# USBC_B.net
KiCad netlist of a schematic drawn in Altium Designer
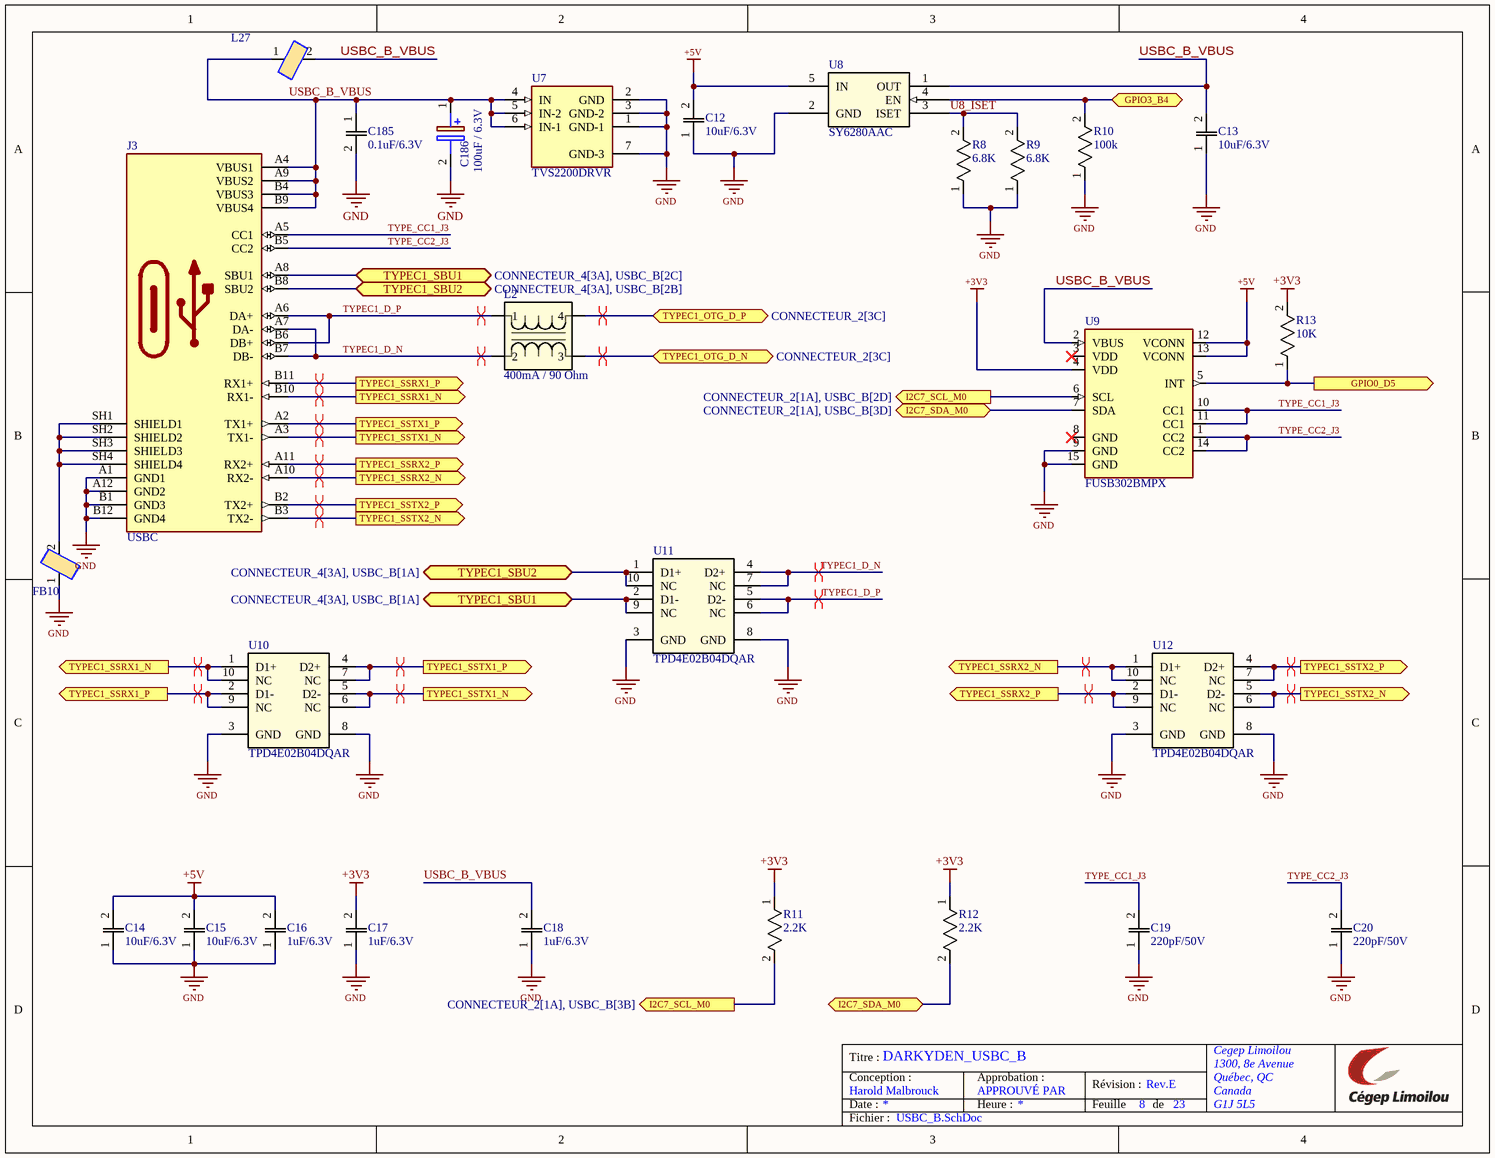
[diagram p0: USBC_B.SchDoc]

(export (version "E")
  (design (tool "Eeschema 10.0.6"))
  (components
    (comp (ref "C12")
      (value "10uF/6.3V")
      (footprint "C0805")
      (fields
        (field (name "MANUFACTURER_PART_NUMBER") "C0805C106K9RACTU")
        (field (name "MOUSER PART NUMBER") "80-C0805C106K9R")
        (field (name "MANUFACTURER") "KEMET")
      )
      (libsource (lib "DARKYDEN") (part "C0805C106K9RACTU"))
    )
    (comp (ref "C13")
      (value "10uF/6.3V")
      (footprint "C0805")
      (fields
        (field (name "MANUFACTURER_PART_NUMBER") "C0805C106K9RACTU")
        (field (name "MOUSER PART NUMBER") "80-C0805C106K9R")
        (field (name "MANUFACTURER") "KEMET")
      )
      (libsource (lib "DARKYDEN") (part "C0805C106K9RACTU"))
    )
    (comp (ref "C14")
      (value "10uF/6.3V")
      (footprint "C0805")
      (fields
        (field (name "MANUFACTURER_PART_NUMBER") "C0805C106K9RACTU")
        (field (name "MOUSER PART NUMBER") "80-C0805C106K9R")
        (field (name "MANUFACTURER") "KEMET")
      )
      (libsource (lib "DARKYDEN") (part "C0805C106K9RACTU"))
    )
    (comp (ref "C15")
      (value "10uF/6.3V")
      (footprint "C0805")
      (fields
        (field (name "MANUFACTURER_PART_NUMBER") "C0805C106K9RACTU")
        (field (name "MOUSER PART NUMBER") "80-C0805C106K9R")
        (field (name "MANUFACTURER") "KEMET")
      )
      (libsource (lib "DARKYDEN") (part "C0805C106K9RACTU"))
    )
    (comp (ref "C16")
      (value "1uF/6.3V")
      (footprint "C0805")
      (description "1 uF, 6.3 V, ± 10%, X7R, 0805 [2012 Metric] Multilayer Ceramic Capacitor,")
      (fields
        (field (name "MANUFACTURER_PART_NUMBER") "C0805C105K9RACTU")
        (field (name "MOUSER PART NUMBER") "80-C0805C105K9R")
      )
      (libsource (lib "DARKYDEN") (part "C0805C105K9RACTU"))
    )
    (comp (ref "C17")
      (value "1uF/6.3V")
      (footprint "C0805")
      (description "1 uF, 6.3 V, ± 10%, X7R, 0805 [2012 Metric] Multilayer Ceramic Capacitor,")
      (fields
        (field (name "MANUFACTURER_PART_NUMBER") "C0805C105K9RACTU")
        (field (name "MOUSER PART NUMBER") "80-C0805C105K9R")
      )
      (libsource (lib "DARKYDEN") (part "C0805C105K9RACTU"))
    )
    (comp (ref "C18")
      (value "1uF/6.3V")
      (footprint "C0805")
      (description "1 uF, 6.3 V, ± 10%, X7R, 0805 [2012 Metric] Multilayer Ceramic Capacitor,")
      (fields
        (field (name "MANUFACTURER_PART_NUMBER") "C0805C105K9RACTU")
        (field (name "MOUSER PART NUMBER") "80-C0805C105K9R")
      )
      (libsource (lib "DARKYDEN") (part "C0805C105K9RACTU"))
    )
    (comp (ref "C19")
      (value "220pF/50V")
      (footprint "C0805")
      (description "Cap Ceramic 220pF 50V X7R 20% Pad SMD 0805 125C T/R")
      (fields
        (field (name "MANUFACTURER") "KEMET")
        (field (name "MANUFACTURER PART NUMBER") "C0805C221M5RACTU")
      )
      (libsource (lib "DARKYDEN") (part "C0805C221M5RACTU"))
    )
    (comp (ref "C20")
      (value "220pF/50V")
      (footprint "C0805")
      (description "Cap Ceramic 220pF 50V X7R 20% Pad SMD 0805 125C T/R")
      (fields
        (field (name "MANUFACTURER") "KEMET")
        (field (name "MANUFACTURER PART NUMBER") "C0805C221M5RACTU")
      )
      (libsource (lib "DARKYDEN") (part "C0805C221M5RACTU"))
    )
    (comp (ref "C185")
      (value "0.1uF/6.3V")
      (footprint "C0805")
      (description "0.1uF 6.3V X7R 10% Pad SMD 0805 125C T/R")
      (fields
        (field (name "MANUFACTURER_PART_NUMBER") "C0805C104K9RACTU")
        (field (name "MOUSER PART NUMBER") "80-C0805C104K9R")
      )
      (libsource (lib "DARKYDEN") (part "C0805C104K9RACTU"))
    )
    (comp (ref "C186")
      (value "100uF / 6.3V")
      (footprint "SamacSys:EEE0GA101SR")
      (description "100uF 6.3V 20% Cap Aluminum Lytic  SMD 0.36 Ohm 240mA 2000h 105C Automotive T/R")
      (fields
        (field (name "MANUFACTURER_PART_NUMBER") "EEE-FPJ101UAR")
        (field (name "MOUSER PART NUMBER") "667-EEE-FPJ101UAR")
      )
      (libsource (lib "SamacSys") (part "EEE-FPJ101UAR"))
    )
    (comp (ref "FB10")
      (value "220R / 100MHz")
      (footprint "SamacSys:BLM18SP221SN1B")
      (description "Ferrite Beads Multi-Layer 220Ohm 25% 100MHz 2A 50mOhm DCR 0603 Paper T/R")
      (fields
        (field (name "MANUFACTURER_PART_NUMBER") "BLM18EG221SN1D")
        (field (name "MOUSER PART NUMBER") "81-BLM18EG221SN1D")
      )
      (libsource (lib "SamacSys") (part "BLM18EG221SN1D"))
    )
    (comp (ref "J3")
      (value "USBC")
      (footprint "USB_C")
      (fields (field (name "MF") "Molex") (field (name "MP") "2012670005"))
      (libsource (lib "DARKYDEN") (part "USBC"))
    )
    (comp (ref "L2")
      (value "400mA / 90 Ohm")
      (footprint "SamacSys:ACM20129002PT002")
      (description "Ferrite Beads Wirewound Common Mode Filter 90Ohm 100MHz 400mA 0805 T/R")
      (fields
        (field (name "MANUFACTURER_PART_NUMBER") "ACM2012-900-2P-T002")
        (field (name "MOUSER PART NUMBER") "810-ACM20129002PT002")
      )
      (libsource (lib "SamacSys") (part "ACM2012-900-2P-T002"))
    )
    (comp (ref "L27")
      (value "FBMJ2125HM210NT")
      (footprint "INDC2012X105N")
      (description "Ferrite Beads Power Chip 21Ohm 30% 100MHz 6A 0.004Ohm DCR 0805 Automotive T/R")
      (fields
        (field (name "MANUFACTURER") "Taiyo Yuden")
        (field (name "MOUSER PART NUMBER") "963-FBMJ2125HM210NT")
      )
      (libsource (lib "SamacSys") (part "FBMJ2125HM210NT"))
    )
    (comp (ref "R8")
      (value "6.8K")
      (footprint "SamacSys:RESC1608X55N")
      (description "6.8 kOhm, ± 5%, 100 mW, 0603 [1608 Metric], Thick Film, General Purpose")
      (fields
        (field (name "MANUFACTURER_PART_NUMBER") "ERJ-3GEYJ682V")
        (field (name "MANUFACTURER") "Panasonic")
      )
      (libsource (lib "DARKYDEN") (part "ERJ-3GEYJ682V"))
    )
    (comp (ref "R9")
      (value "6.8K")
      (footprint "SamacSys:RESC1608X55N")
      (description "6.8 kOhm, ± 5%, 100 mW, 0603 [1608 Metric], Thick Film, General Purpose")
      (fields
        (field (name "MANUFACTURER_PART_NUMBER") "ERJ-3GEYJ682V")
        (field (name "MANUFACTURER") "Panasonic")
      )
      (libsource (lib "DARKYDEN") (part "ERJ-3GEYJ682V"))
    )
    (comp (ref "R10")
      (value "100k")
      (footprint "SamacSys:RESC1608X55N")
      (description "100K Ohm 5%  Res Thick Film 0603 1/10W +/-200ppm/ßC Molded SMD Punched Carrier T/R")
      (fields
        (field (name "MANUFACTURER_PART_NUMBER") "ERJ-3GEYJ104V")
        (field (name "MOUSER PART NUMBER") "667-ERJ-3GEYJ104V")
      )
      (libsource (lib "DARKYDEN") (part "ERJ-3GEYJ104V"))
    )
    (comp (ref "R11")
      (value "2.2K")
      (footprint "SamacSys:RESC1608X55N")
      (description "2.2 kOhm, ï¿½ 5%, 100 mW, 0603 [1608 Metric], Thick Film, General Purpose")
      (fields
        (field (name "MANUFACTURER_PART_NUMBER") "ERJ-3GEYJ222V")
        (field (name "MOUSER PART NUMBER") "667-ERJ-3GEYJ222V")
      )
      (libsource (lib "DARKYDEN") (part "ERJ-3GEYJ222V"))
    )
    (comp (ref "R12")
      (value "2.2K")
      (footprint "SamacSys:RESC1608X55N")
      (description "2.2 kOhm, ï¿½ 5%, 100 mW, 0603 [1608 Metric], Thick Film, General Purpose")
      (fields
        (field (name "MANUFACTURER_PART_NUMBER") "ERJ-3GEYJ222V")
        (field (name "MOUSER PART NUMBER") "667-ERJ-3GEYJ222V")
      )
      (libsource (lib "DARKYDEN") (part "ERJ-3GEYJ222V"))
    )
    (comp (ref "R13")
      (value "10K")
      (footprint "SamacSys:RESC1608X55N")
      (description "10K Ohm 5% Res Thick Film 0603  0.1W(1/10W) ±200ppm/C Pad SMD Automotive T/R")
      (fields
        (field (name "MANUFACTURER_PART_NUMBER") "ERJ-3GEYJ103V")
        (field (name "MOUSER PART NUMBER") "667-ERJ-3GEYJ103V")
      )
      (libsource (lib "DARKYDEN") (part "ERJ-3GEYJ103V"))
    )
    (comp (ref "U7")
      (value "TVS2200DRVR")
      (footprint "SON65P200X200X80-7N")
      (description "ESD Suppressors / TVS Diodes 22V flat-clamp surge protection device 6-WSON -40 to 125")
      (fields (field (name "MF") "Texas Instruments"))
      (libsource (lib "TVS2200") (part "TVS2200DRVR"))
    )
    (comp (ref "U8")
      (value "SY6280AAC")
      (footprint "SamacSys:SOT95P285X140-5N")
      (description "2.4V~5.5V 80mΩ Active High 1 High-side switch SOT-23-5 Power Distribution Switches ROHS")
      (libsource (lib "SamacSys") (part "SY6280AAC"))
    )
    (comp (ref "U9")
      (value "FUSB302BMPX")
      (footprint "SamacSys:QFN50P250X250X80-15N")
      (description "USB Controller USB 3.1 USB Interface 14-MLP (2.5x2.5)")
      (fields (field (name "MOUSER PART NUMBER") "512-FUSB302BMPX"))
      (libsource (lib "SamacSys") (part "FUSB302BMPX"))
    )
    (comp (ref "U10")
      (value "TPD4E02B04DQAR")
      (footprint "DQA0010A")
      (description "TVS DIODE 3.6V 8.8V 10USON / 4-Channel ESD Protection Diode for USB Type-C and HDMI 2.0")
      (fields (field (name "MANUFACTURER") "Texas Instruments"))
      (libsource (lib "TPD4E02B04DQAR") (part "TPD4E02B04DQAR"))
    )
    (comp (ref "U11")
      (value "TPD4E02B04DQAR")
      (footprint "DQA0010A")
      (description "TVS DIODE 3.6V 8.8V 10USON / 4-Channel ESD Protection Diode for USB Type-C and HDMI 2.0")
      (fields (field (name "MANUFACTURER") "Texas Instruments"))
      (libsource (lib "TPD4E02B04DQAR") (part "TPD4E02B04DQAR"))
    )
    (comp (ref "U12")
      (value "TPD4E02B04DQAR")
      (footprint "DQA0010A")
      (description "TVS DIODE 3.6V 8.8V 10USON / 4-Channel ESD Protection Diode for USB Type-C and HDMI 2.0")
      (fields (field (name "MANUFACTURER") "Texas Instruments"))
      (libsource (lib "TPD4E02B04DQAR") (part "TPD4E02B04DQAR"))
    )
  )
  (nets
    (net (code "1") (name "+3V3") (class "Default")
      (node (ref "C17") (pin "2") (pinfunction "2_2") (pintype "passive"))
      (node (ref "R11") (pin "1") (pinfunction "1_1") (pintype "passive"))
      (node (ref "R12") (pin "1") (pinfunction "1_1") (pintype "passive"))
      (node (ref "R13") (pin "2") (pinfunction "2_2") (pintype "passive"))
      (node (ref "U9") (pin "4") (pinfunction "VDD_4") (pintype "power_in"))
    )
    (net (code "2") (name "+5V") (class "Default")
      (node (ref "C12") (pin "2") (pinfunction "2_2") (pintype "passive"))
      (node (ref "C14") (pin "2") (pinfunction "2_2") (pintype "passive"))
      (node (ref "C15") (pin "2") (pinfunction "2_2") (pintype "passive"))
      (node (ref "C16") (pin "2") (pinfunction "2_2") (pintype "passive"))
      (node (ref "U8") (pin "5") (pinfunction "IN_5") (pintype "power_in"))
      (node (ref "U9") (pin "12") (pinfunction "VCONN_12") (pintype "power_in"))
      (node (ref "U9") (pin "13") (pinfunction "VCONN_13") (pintype "power_in"))
    )
    (net (code "3") (name "/GPIO0_D5") (class "Default")
      (node (ref "R13") (pin "1") (pinfunction "1_1") (pintype "passive"))
      (node (ref "U9") (pin "5") (pinfunction "INT_5") (pintype "output"))
    )
    (net (code "4") (name "/GPIO3_B4") (class "Default")
      (node (ref "R10") (pin "2") (pinfunction "2_2") (pintype "passive"))
      (node (ref "U8") (pin "4") (pinfunction "EN_4") (pintype "input"))
    )
    (net (code "5") (name "/I2C7_SCL_M0") (class "Default")
      (node (ref "R11") (pin "2") (pinfunction "2_2") (pintype "passive"))
      (node (ref "U9") (pin "6") (pinfunction "SCL_6") (pintype "input"))
    )
    (net (code "6") (name "/I2C7_SDA_M0") (class "Default")
      (node (ref "R12") (pin "2") (pinfunction "2_2") (pintype "passive"))
      (node (ref "U9") (pin "7") (pinfunction "SDA_7") (pintype "bidirectional"))
    )
    (net (code "7") (name "/TYPEC1_D_N") (class "Default")
      (node (ref "J3") (pin "A7") (pinfunction "DA-_A7") (pintype "bidirectional"))
      (node (ref "J3") (pin "B7") (pinfunction "DB-_B7") (pintype "bidirectional"))
      (node (ref "L2") (pin "2") (pinfunction "2_2") (pintype "passive"))
      (node (ref "U11") (pin "4") (pinfunction "D2+_4") (pintype "passive"))
      (node (ref "U11") (pin "7") (pinfunction "NC_7") (pintype "passive"))
    )
    (net (code "8") (name "/TYPEC1_D_P") (class "Default")
      (node (ref "J3") (pin "A6") (pinfunction "DA+_A6") (pintype "bidirectional"))
      (node (ref "J3") (pin "B6") (pinfunction "DB+_B6") (pintype "bidirectional"))
      (node (ref "L2") (pin "1") (pinfunction "1_1") (pintype "passive"))
      (node (ref "U11") (pin "5") (pinfunction "D2-_5") (pintype "passive"))
      (node (ref "U11") (pin "6") (pinfunction "NC_6") (pintype "passive"))
    )
    (net (code "9") (name "/TYPEC1_OTG_D_N") (class "Default")
      (node (ref "L2") (pin "3") (pinfunction "3_3") (pintype "passive"))
    )
    (net (code "10") (name "/TYPEC1_OTG_D_P") (class "Default")
      (node (ref "L2") (pin "4") (pinfunction "4_4") (pintype "passive"))
    )
    (net (code "11") (name "/TYPEC1_SBU1") (class "Default")
      (node (ref "J3") (pin "A8") (pinfunction "SBU1_A8") (pintype "bidirectional"))
      (node (ref "U11") (pin "2") (pinfunction "D1-_2") (pintype "passive"))
      (node (ref "U11") (pin "9") (pinfunction "NC_9") (pintype "passive"))
    )
    (net (code "12") (name "/TYPEC1_SBU2") (class "Default")
      (node (ref "J3") (pin "B8") (pinfunction "SBU2_B8") (pintype "bidirectional"))
      (node (ref "U11") (pin "1") (pinfunction "D1+_1") (pintype "passive"))
      (node (ref "U11") (pin "10") (pinfunction "NC_10") (pintype "passive"))
    )
    (net (code "13") (name "/TYPEC1_SSRX1_N") (class "Default")
      (node (ref "J3") (pin "B10") (pinfunction "RX1-_B10") (pintype "input"))
      (node (ref "U10") (pin "1") (pinfunction "D1+_1") (pintype "passive"))
      (node (ref "U10") (pin "10") (pinfunction "NC_10") (pintype "passive"))
    )
    (net (code "14") (name "/TYPEC1_SSRX1_P") (class "Default")
      (node (ref "J3") (pin "B11") (pinfunction "RX1+_B11") (pintype "input"))
      (node (ref "U10") (pin "2") (pinfunction "D1-_2") (pintype "passive"))
      (node (ref "U10") (pin "9") (pinfunction "NC_9") (pintype "passive"))
    )
    (net (code "15") (name "/TYPEC1_SSRX2_N") (class "Default")
      (node (ref "J3") (pin "A10") (pinfunction "RX2-_A10") (pintype "input"))
      (node (ref "U12") (pin "1") (pinfunction "D1+_1") (pintype "passive"))
      (node (ref "U12") (pin "10") (pinfunction "NC_10") (pintype "passive"))
    )
    (net (code "16") (name "/TYPEC1_SSRX2_P") (class "Default")
      (node (ref "J3") (pin "A11") (pinfunction "RX2+_A11") (pintype "input"))
      (node (ref "U12") (pin "2") (pinfunction "D1-_2") (pintype "passive"))
      (node (ref "U12") (pin "9") (pinfunction "NC_9") (pintype "passive"))
    )
    (net (code "17") (name "/TYPEC1_SSTX1_N") (class "Default")
      (node (ref "J3") (pin "A3") (pinfunction "TX1-_A3") (pintype "output"))
      (node (ref "U10") (pin "5") (pinfunction "D2-_5") (pintype "passive"))
      (node (ref "U10") (pin "6") (pinfunction "NC_6") (pintype "passive"))
    )
    (net (code "18") (name "/TYPEC1_SSTX1_P") (class "Default")
      (node (ref "J3") (pin "A2") (pinfunction "TX1+_A2") (pintype "output"))
      (node (ref "U10") (pin "4") (pinfunction "D2+_4") (pintype "passive"))
      (node (ref "U10") (pin "7") (pinfunction "NC_7") (pintype "passive"))
    )
    (net (code "19") (name "/TYPEC1_SSTX2_N") (class "Default")
      (node (ref "J3") (pin "B3") (pinfunction "TX2-_B3") (pintype "output"))
      (node (ref "U12") (pin "5") (pinfunction "D2-_5") (pintype "passive"))
      (node (ref "U12") (pin "6") (pinfunction "NC_6") (pintype "passive"))
    )
    (net (code "20") (name "/TYPEC1_SSTX2_P") (class "Default")
      (node (ref "J3") (pin "B2") (pinfunction "TX2+_B2") (pintype "output"))
      (node (ref "U12") (pin "4") (pinfunction "D2+_4") (pintype "passive"))
      (node (ref "U12") (pin "7") (pinfunction "NC_7") (pintype "passive"))
    )
    (net (code "21") (name "/TYPE_CC1_J3") (class "Default")
      (node (ref "C19") (pin "2") (pinfunction "2_2") (pintype "passive"))
      (node (ref "J3") (pin "A5") (pinfunction "CC1_A5") (pintype "bidirectional"))
      (node (ref "U9") (pin "10") (pinfunction "CC1_10") (pintype "bidirectional"))
      (node (ref "U9") (pin "11") (pinfunction "CC1_11") (pintype "bidirectional"))
    )
    (net (code "22") (name "/TYPE_CC2_J3") (class "Default")
      (node (ref "C20") (pin "2") (pinfunction "2_2") (pintype "passive"))
      (node (ref "J3") (pin "B5") (pinfunction "CC2_B5") (pintype "bidirectional"))
      (node (ref "U9") (pin "1") (pinfunction "CC2_1") (pintype "bidirectional"))
      (node (ref "U9") (pin "14") (pinfunction "CC2_14") (pintype "bidirectional"))
    )
    (net (code "23") (name "/U8_ISET") (class "Default")
      (node (ref "R8") (pin "2") (pinfunction "2_2") (pintype "passive"))
      (node (ref "R9") (pin "2") (pinfunction "2_2") (pintype "passive"))
      (node (ref "U8") (pin "3") (pinfunction "ISET_3") (pintype "passive"))
    )
    (net (code "24") (name "/USBC_B_VBUS") (class "Default")
      (node (ref "C13") (pin "2") (pinfunction "2_2") (pintype "passive"))
      (node (ref "C18") (pin "2") (pinfunction "2_2") (pintype "passive"))
      (node (ref "C185") (pin "1") (pinfunction "1_1") (pintype "passive"))
      (node (ref "C186") (pin "1") (pinfunction "+_1") (pintype "passive"))
      (node (ref "J3") (pin "A4") (pinfunction "VBUS1_A4") (pintype "power_in"))
      (node (ref "J3") (pin "A9") (pinfunction "VBUS2_A9") (pintype "power_in"))
      (node (ref "J3") (pin "B4") (pinfunction "VBUS3_B4") (pintype "power_in"))
      (node (ref "J3") (pin "B9") (pinfunction "VBUS4_B9") (pintype "power_in"))
      (node (ref "L27") (pin "1") (pinfunction "1_1") (pintype "passive"))
      (node (ref "L27") (pin "2") (pinfunction "2_2") (pintype "passive"))
      (node (ref "U7") (pin "4") (pinfunction "IN_4") (pintype "input"))
      (node (ref "U7") (pin "5") (pinfunction "IN-2_5") (pintype "input"))
      (node (ref "U7") (pin "6") (pinfunction "IN-1_6") (pintype "input"))
      (node (ref "U8") (pin "1") (pinfunction "OUT_1") (pintype "power_in"))
      (node (ref "U9") (pin "2") (pinfunction "VBUS_2") (pintype "input"))
    )
    (net (code "25") (name "GND") (class "Default")
      (node (ref "C12") (pin "1") (pinfunction "1_1") (pintype "passive"))
      (node (ref "C13") (pin "1") (pinfunction "1_1") (pintype "passive"))
      (node (ref "C14") (pin "1") (pinfunction "1_1") (pintype "passive"))
      (node (ref "C15") (pin "1") (pinfunction "1_1") (pintype "passive"))
      (node (ref "C16") (pin "1") (pinfunction "1_1") (pintype "passive"))
      (node (ref "C17") (pin "1") (pinfunction "1_1") (pintype "passive"))
      (node (ref "C18") (pin "1") (pinfunction "1_1") (pintype "passive"))
      (node (ref "C185") (pin "2") (pinfunction "2_2") (pintype "passive"))
      (node (ref "C186") (pin "2") (pinfunction "-_2") (pintype "passive"))
      (node (ref "C19") (pin "1") (pinfunction "1_1") (pintype "passive"))
      (node (ref "C20") (pin "1") (pinfunction "1_1") (pintype "passive"))
      (node (ref "FB10") (pin "1") (pinfunction "1_1") (pintype "passive"))
      (node (ref "J3") (pin "A1") (pinfunction "GND1_A1") (pintype "passive"))
      (node (ref "J3") (pin "A12") (pinfunction "GND2_A12") (pintype "passive"))
      (node (ref "J3") (pin "B1") (pinfunction "GND3_B1") (pintype "passive"))
      (node (ref "J3") (pin "B12") (pinfunction "GND4_B12") (pintype "passive"))
      (node (ref "R10") (pin "1") (pinfunction "1_1") (pintype "passive"))
      (node (ref "R8") (pin "1") (pinfunction "1_1") (pintype "passive"))
      (node (ref "R9") (pin "1") (pinfunction "1_1") (pintype "passive"))
      (node (ref "U10") (pin "3") (pinfunction "GND_3") (pintype "passive"))
      (node (ref "U10") (pin "8") (pinfunction "GND_8") (pintype "passive"))
      (node (ref "U11") (pin "3") (pinfunction "GND_3") (pintype "passive"))
      (node (ref "U11") (pin "8") (pinfunction "GND_8") (pintype "passive"))
      (node (ref "U12") (pin "3") (pinfunction "GND_3") (pintype "passive"))
      (node (ref "U12") (pin "8") (pinfunction "GND_8") (pintype "passive"))
      (node (ref "U7") (pin "1") (pinfunction "GND-1_1") (pintype "passive"))
      (node (ref "U7") (pin "2") (pinfunction "GND_2") (pintype "passive"))
      (node (ref "U7") (pin "3") (pinfunction "GND-2_3") (pintype "passive"))
      (node (ref "U7") (pin "7") (pinfunction "GND-3_7") (pintype "passive"))
      (node (ref "U8") (pin "2") (pinfunction "GND_2") (pintype "passive"))
      (node (ref "U9") (pin "15") (pinfunction "GND_15") (pintype "passive"))
      (node (ref "U9") (pin "9") (pinfunction "GND_9") (pintype "passive"))
    )
    (net (code "26") (name "Net-(J3-SHIELD1)") (class "Default")
      (node (ref "FB10") (pin "2") (pinfunction "2_2") (pintype "passive"))
      (node (ref "J3") (pin "SH1") (pinfunction "SHIELD1_SH1") (pintype "passive"))
      (node (ref "J3") (pin "SH2") (pinfunction "SHIELD2_SH2") (pintype "passive"))
      (node (ref "J3") (pin "SH3") (pinfunction "SHIELD3_SH3") (pintype "passive"))
      (node (ref "J3") (pin "SH4") (pinfunction "SHIELD4_SH4") (pintype "passive"))
    )
    (net (code "27") (name "unconnected-(U9-GND-Pad8)") (class "Default")
      (node (ref "U9") (pin "8") (pinfunction "GND_8") (pintype "passive+no_connect"))
    )
    (net (code "28") (name "unconnected-(U9-VDD-Pad3)") (class "Default")
      (node (ref "U9") (pin "3") (pinfunction "VDD_3") (pintype "power_in+no_connect"))
    )
  )
)
